# Temp_Bank.net
KiCad netlist of a schematic drawn in Altium Designer
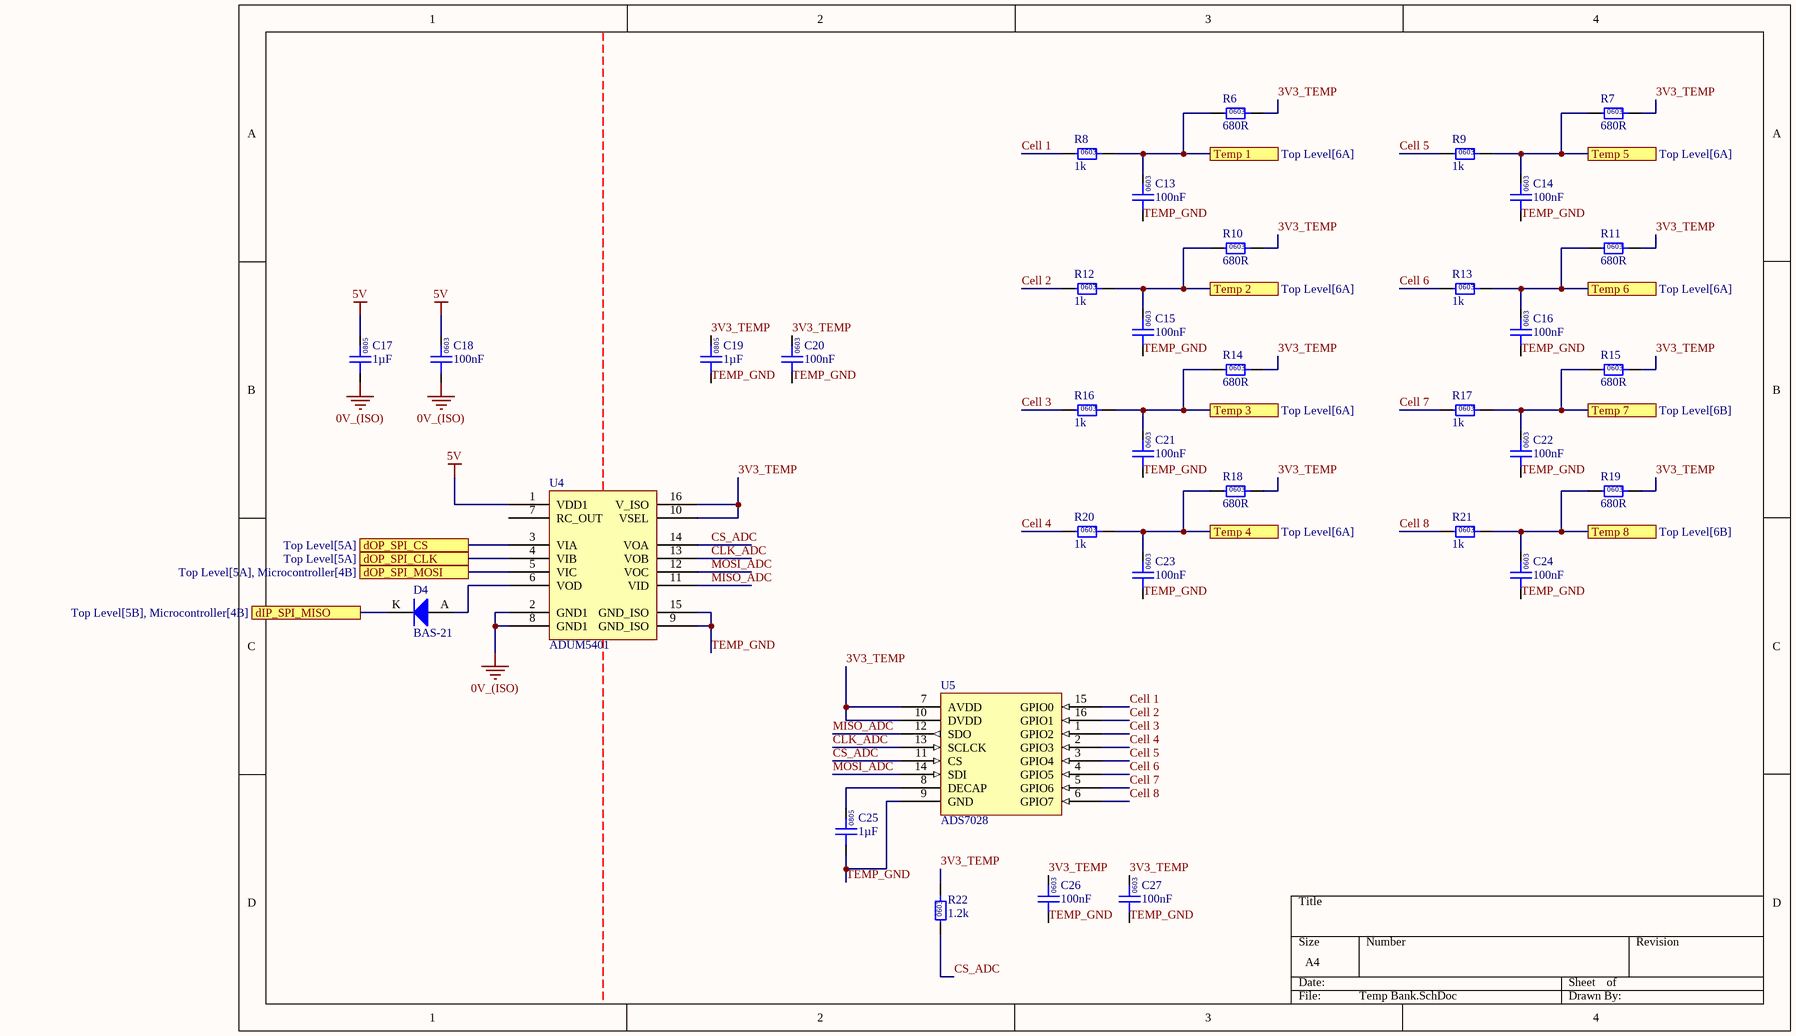
[diagram p0: Temp Bank.SchDoc]

(export (version "E")
  (design (tool "Eeschema 10.0.6"))
  (components
    (comp (ref "C13")
      (value "100nF")
      (footprint "0603")
      (fields
        (field (name "PART NUMBER") "GCM188L81H104KA57D")
        (field (name "MANUFACTURER") "muRata")
        (field (name "TOLERANCE") "±10%")
      )
      (libsource (lib "ts_standard_library") (part "Capacitor 0603"))
    )
    (comp (ref "C14")
      (value "100nF")
      (footprint "0603")
      (fields
        (field (name "PART NUMBER") "GCM188L81H104KA57D")
        (field (name "MANUFACTURER") "muRata")
        (field (name "TOLERANCE") "±10%")
      )
      (libsource (lib "ts_standard_library") (part "Capacitor 0603"))
    )
    (comp (ref "C15")
      (value "100nF")
      (footprint "0603")
      (fields
        (field (name "PART NUMBER") "GCM188L81H104KA57D")
        (field (name "MANUFACTURER") "muRata")
        (field (name "TOLERANCE") "±10%")
      )
      (libsource (lib "ts_standard_library") (part "Capacitor 0603"))
    )
    (comp (ref "C16")
      (value "100nF")
      (footprint "0603")
      (fields
        (field (name "PART NUMBER") "GCM188L81H104KA57D")
        (field (name "MANUFACTURER") "muRata")
        (field (name "TOLERANCE") "±10%")
      )
      (libsource (lib "ts_standard_library") (part "Capacitor 0603"))
    )
    (comp (ref "C17")
      (value "1µF")
      (footprint "0805")
      (fields
        (field (name "PART NUMBER") "GCM21BR71H105KA03L")
        (field (name "MANUFACTURER") "muRata")
        (field (name "TOLERANCE") "±10%")
      )
      (libsource (lib "ts_standard_library") (part "Capacitor 0805"))
    )
    (comp (ref "C18")
      (value "100nF")
      (footprint "0603")
      (fields
        (field (name "PART NUMBER") "GCM188L81H104KA57D")
        (field (name "MANUFACTURER") "muRata")
        (field (name "TOLERANCE") "±10%")
      )
      (libsource (lib "ts_standard_library") (part "Capacitor 0603"))
    )
    (comp (ref "C19")
      (value "1µF")
      (footprint "0805")
      (fields
        (field (name "PART NUMBER") "GCM21BR71H105KA03L")
        (field (name "MANUFACTURER") "muRata")
        (field (name "TOLERANCE") "±10%")
      )
      (libsource (lib "ts_standard_library") (part "Capacitor 0805"))
    )
    (comp (ref "C20")
      (value "100nF")
      (footprint "0603")
      (fields
        (field (name "PART NUMBER") "GCM188L81H104KA57D")
        (field (name "MANUFACTURER") "muRata")
        (field (name "TOLERANCE") "±10%")
      )
      (libsource (lib "ts_standard_library") (part "Capacitor 0603"))
    )
    (comp (ref "C21")
      (value "100nF")
      (footprint "0603")
      (fields
        (field (name "PART NUMBER") "GCM188L81H104KA57D")
        (field (name "MANUFACTURER") "muRata")
        (field (name "TOLERANCE") "±10%")
      )
      (libsource (lib "ts_standard_library") (part "Capacitor 0603"))
    )
    (comp (ref "C22")
      (value "100nF")
      (footprint "0603")
      (fields
        (field (name "PART NUMBER") "GCM188L81H104KA57D")
        (field (name "MANUFACTURER") "muRata")
        (field (name "TOLERANCE") "±10%")
      )
      (libsource (lib "ts_standard_library") (part "Capacitor 0603"))
    )
    (comp (ref "C23")
      (value "100nF")
      (footprint "0603")
      (fields
        (field (name "PART NUMBER") "GCM188L81H104KA57D")
        (field (name "MANUFACTURER") "muRata")
        (field (name "TOLERANCE") "±10%")
      )
      (libsource (lib "ts_standard_library") (part "Capacitor 0603"))
    )
    (comp (ref "C24")
      (value "100nF")
      (footprint "0603")
      (fields
        (field (name "PART NUMBER") "GCM188L81H104KA57D")
        (field (name "MANUFACTURER") "muRata")
        (field (name "TOLERANCE") "±10%")
      )
      (libsource (lib "ts_standard_library") (part "Capacitor 0603"))
    )
    (comp (ref "C25")
      (value "1µF")
      (footprint "0805")
      (fields
        (field (name "PART NUMBER") "GCM21BR71H105KA03L")
        (field (name "MANUFACTURER") "muRata")
        (field (name "TOLERANCE") "±10%")
      )
      (libsource (lib "ts_standard_library") (part "Capacitor 0805"))
    )
    (comp (ref "C26")
      (value "100nF")
      (footprint "0603")
      (fields
        (field (name "PART NUMBER") "GCM188L81H104KA57D")
        (field (name "MANUFACTURER") "muRata")
        (field (name "TOLERANCE") "±10%")
      )
      (libsource (lib "ts_standard_library") (part "Capacitor 0603"))
    )
    (comp (ref "C27")
      (value "100nF")
      (footprint "0603")
      (fields
        (field (name "PART NUMBER") "GCM188L81H104KA57D")
        (field (name "MANUFACTURER") "muRata")
        (field (name "TOLERANCE") "±10%")
      )
      (libsource (lib "ts_standard_library") (part "Capacitor 0603"))
    )
    (comp (ref "D4")
      (value "BAS-21")
      (footprint "NEXPERIA_SOT23")
      (fields (field (name "MANUFACTURER") "Nexperia USA Inc."))
      (libsource (lib "ts_standard_library") (part "Diode"))
    )
    (comp (ref "R6")
      (value "680R")
      (footprint "0603")
      (fields
        (field (name "PART NUMBER") "RC0603JR-13680RL")
        (field (name "MANUFACTURER") "YAGEO")
        (field (name "TOLERANCE") "0.01")
      )
      (libsource (lib "ts_standard_library") (part "Resistor 0603"))
    )
    (comp (ref "R7")
      (value "680R")
      (footprint "0603")
      (fields
        (field (name "PART NUMBER") "RC0603JR-13680RL")
        (field (name "MANUFACTURER") "YAGEO")
        (field (name "TOLERANCE") "0.01")
      )
      (libsource (lib "ts_standard_library") (part "Resistor 0603"))
    )
    (comp (ref "R8")
      (value "1k")
      (footprint "0603")
      (fields
        (field (name "PART NUMBER") "RC0603FR-071KL")
        (field (name "MANUFACTURER") "YAGEO")
        (field (name "TOLERANCE") "0.01")
      )
      (libsource (lib "ts_standard_library") (part "Resistor 0603"))
    )
    (comp (ref "R9")
      (value "1k")
      (footprint "0603")
      (fields
        (field (name "PART NUMBER") "RC0603FR-071KL")
        (field (name "MANUFACTURER") "YAGEO")
        (field (name "TOLERANCE") "0.01")
      )
      (libsource (lib "ts_standard_library") (part "Resistor 0603"))
    )
    (comp (ref "R10")
      (value "680R")
      (footprint "0603")
      (fields
        (field (name "PART NUMBER") "RC0603JR-13680RL")
        (field (name "MANUFACTURER") "YAGEO")
        (field (name "TOLERANCE") "0.01")
      )
      (libsource (lib "ts_standard_library") (part "Resistor 0603"))
    )
    (comp (ref "R11")
      (value "680R")
      (footprint "0603")
      (fields
        (field (name "PART NUMBER") "RC0603JR-13680RL")
        (field (name "MANUFACTURER") "YAGEO")
        (field (name "TOLERANCE") "0.01")
      )
      (libsource (lib "ts_standard_library") (part "Resistor 0603"))
    )
    (comp (ref "R12")
      (value "1k")
      (footprint "0603")
      (fields
        (field (name "PART NUMBER") "RC0603FR-071KL")
        (field (name "MANUFACTURER") "YAGEO")
        (field (name "TOLERANCE") "0.01")
      )
      (libsource (lib "ts_standard_library") (part "Resistor 0603"))
    )
    (comp (ref "R13")
      (value "1k")
      (footprint "0603")
      (fields
        (field (name "PART NUMBER") "RC0603FR-071KL")
        (field (name "MANUFACTURER") "YAGEO")
        (field (name "TOLERANCE") "0.01")
      )
      (libsource (lib "ts_standard_library") (part "Resistor 0603"))
    )
    (comp (ref "R14")
      (value "680R")
      (footprint "0603")
      (fields
        (field (name "PART NUMBER") "RC0603JR-13680RL")
        (field (name "MANUFACTURER") "YAGEO")
        (field (name "TOLERANCE") "0.01")
      )
      (libsource (lib "ts_standard_library") (part "Resistor 0603"))
    )
    (comp (ref "R15")
      (value "680R")
      (footprint "0603")
      (fields
        (field (name "PART NUMBER") "RC0603JR-13680RL")
        (field (name "MANUFACTURER") "YAGEO")
        (field (name "TOLERANCE") "0.01")
      )
      (libsource (lib "ts_standard_library") (part "Resistor 0603"))
    )
    (comp (ref "R16")
      (value "1k")
      (footprint "0603")
      (fields
        (field (name "PART NUMBER") "RC0603FR-071KL")
        (field (name "MANUFACTURER") "YAGEO")
        (field (name "TOLERANCE") "0.01")
      )
      (libsource (lib "ts_standard_library") (part "Resistor 0603"))
    )
    (comp (ref "R17")
      (value "1k")
      (footprint "0603")
      (fields
        (field (name "PART NUMBER") "RC0603FR-071KL")
        (field (name "MANUFACTURER") "YAGEO")
        (field (name "TOLERANCE") "0.01")
      )
      (libsource (lib "ts_standard_library") (part "Resistor 0603"))
    )
    (comp (ref "R18")
      (value "680R")
      (footprint "0603")
      (fields
        (field (name "PART NUMBER") "RC0603JR-13680RL")
        (field (name "MANUFACTURER") "YAGEO")
        (field (name "TOLERANCE") "0.01")
      )
      (libsource (lib "ts_standard_library") (part "Resistor 0603"))
    )
    (comp (ref "R19")
      (value "680R")
      (footprint "0603")
      (fields
        (field (name "PART NUMBER") "RC0603JR-13680RL")
        (field (name "MANUFACTURER") "YAGEO")
        (field (name "TOLERANCE") "0.01")
      )
      (libsource (lib "ts_standard_library") (part "Resistor 0603"))
    )
    (comp (ref "R20")
      (value "1k")
      (footprint "0603")
      (fields
        (field (name "PART NUMBER") "RC0603FR-071KL")
        (field (name "MANUFACTURER") "YAGEO")
        (field (name "TOLERANCE") "0.01")
      )
      (libsource (lib "ts_standard_library") (part "Resistor 0603"))
    )
    (comp (ref "R21")
      (value "1k")
      (footprint "0603")
      (fields
        (field (name "PART NUMBER") "RC0603FR-071KL")
        (field (name "MANUFACTURER") "YAGEO")
        (field (name "TOLERANCE") "0.01")
      )
      (libsource (lib "ts_standard_library") (part "Resistor 0603"))
    )
    (comp (ref "R22")
      (value "1.2k")
      (footprint "0603")
      (fields
        (field (name "PART NUMBER") "RC0603JR-071K2L")
        (field (name "MANUFACTURER") "YAGEO")
        (field (name "TOLERANCE") "0.01")
      )
      (libsource (lib "ts_standard_library") (part "Resistor 0603"))
    )
    (comp (ref "U4")
      (value "ADUM5401")
      (footprint "AD 16-SOIC")
      (description "Quad Channel 2.5kV Digital Isolator with isoPower")
      (fields (field (name "MANUFACTURER") "Analogue Devices"))
      (libsource (lib "ts_standard_library") (part "ADUM5401"))
    )
    (comp (ref "U5")
      (value "ADS7028")
      (footprint "WFQN-16")
      (description "IC ADC 12BIT SAR 16WQFN")
      (fields (field (name "PART NUMBER") "ADS7028IRTER") (field (name "MANUFACTURER") "Texas Instruments"))
      (libsource (lib "ts_standard_library") (part "ADS7028IRTER"))
    )
  )
  (nets
    (net (code "1") (name "/3V3_TEMP") (class "Default")
      (node (ref "C19") (pin "2") (pinfunction "2_2") (pintype "passive"))
      (node (ref "C20") (pin "2") (pinfunction "2_2") (pintype "passive"))
      (node (ref "C26") (pin "2") (pinfunction "2_2") (pintype "passive"))
      (node (ref "C27") (pin "2") (pinfunction "2_2") (pintype "passive"))
      (node (ref "R10") (pin "2") (pinfunction "2_2") (pintype "passive"))
      (node (ref "R11") (pin "2") (pinfunction "2_2") (pintype "passive"))
      (node (ref "R14") (pin "2") (pinfunction "2_2") (pintype "passive"))
      (node (ref "R15") (pin "2") (pinfunction "2_2") (pintype "passive"))
      (node (ref "R18") (pin "2") (pinfunction "2_2") (pintype "passive"))
      (node (ref "R19") (pin "2") (pinfunction "2_2") (pintype "passive"))
      (node (ref "R22") (pin "2") (pinfunction "2_2") (pintype "passive"))
      (node (ref "R6") (pin "2") (pinfunction "2_2") (pintype "passive"))
      (node (ref "R7") (pin "2") (pinfunction "2_2") (pintype "passive"))
      (node (ref "U4") (pin "10") (pinfunction "VSEL_10") (pintype "passive"))
      (node (ref "U4") (pin "16") (pinfunction "V_ISO_16") (pintype "passive"))
      (node (ref "U5") (pin "10") (pinfunction "DVDD_10") (pintype "power_in"))
      (node (ref "U5") (pin "7") (pinfunction "AVDD_7") (pintype "power_in"))
    )
    (net (code "2") (name "/CLK_ADC") (class "Default")
      (node (ref "U4") (pin "13") (pinfunction "VOB_13") (pintype "passive"))
      (node (ref "U5") (pin "13") (pinfunction "SCLCK_13") (pintype "input"))
    )
    (net (code "3") (name "/CS_ADC") (class "Default")
      (node (ref "R22") (pin "1") (pinfunction "1_1") (pintype "passive"))
      (node (ref "U4") (pin "14") (pinfunction "VOA_14") (pintype "passive"))
      (node (ref "U5") (pin "11") (pinfunction "CS_11") (pintype "input"))
    )
    (net (code "4") (name "/Cell 1") (class "Default")
      (node (ref "R8") (pin "1") (pinfunction "1_1") (pintype "passive"))
      (node (ref "U5") (pin "15") (pinfunction "GPIO0_15") (pintype "input"))
    )
    (net (code "5") (name "/Cell 2") (class "Default")
      (node (ref "R12") (pin "1") (pinfunction "1_1") (pintype "passive"))
      (node (ref "U5") (pin "16") (pinfunction "GPIO1_16") (pintype "input"))
    )
    (net (code "6") (name "/Cell 3") (class "Default")
      (node (ref "R16") (pin "1") (pinfunction "1_1") (pintype "passive"))
      (node (ref "U5") (pin "1") (pinfunction "GPIO2_1") (pintype "input"))
    )
    (net (code "7") (name "/Cell 4") (class "Default")
      (node (ref "R20") (pin "1") (pinfunction "1_1") (pintype "passive"))
      (node (ref "U5") (pin "2") (pinfunction "GPIO3_2") (pintype "input"))
    )
    (net (code "8") (name "/Cell 5") (class "Default")
      (node (ref "R9") (pin "1") (pinfunction "1_1") (pintype "passive"))
      (node (ref "U5") (pin "3") (pinfunction "GPIO4_3") (pintype "input"))
    )
    (net (code "9") (name "/Cell 6") (class "Default")
      (node (ref "R13") (pin "1") (pinfunction "1_1") (pintype "passive"))
      (node (ref "U5") (pin "4") (pinfunction "GPIO5_4") (pintype "input"))
    )
    (net (code "10") (name "/Cell 7") (class "Default")
      (node (ref "R17") (pin "1") (pinfunction "1_1") (pintype "passive"))
      (node (ref "U5") (pin "5") (pinfunction "GPIO6_5") (pintype "input"))
    )
    (net (code "11") (name "/Cell 8") (class "Default")
      (node (ref "R21") (pin "1") (pinfunction "1_1") (pintype "passive"))
      (node (ref "U5") (pin "6") (pinfunction "GPIO7_6") (pintype "input"))
    )
    (net (code "12") (name "/MISO_ADC") (class "Default")
      (node (ref "U4") (pin "11") (pinfunction "VID_11") (pintype "passive"))
      (node (ref "U5") (pin "12") (pinfunction "SDO_12") (pintype "output"))
    )
    (net (code "13") (name "/MOSI_ADC") (class "Default")
      (node (ref "U4") (pin "12") (pinfunction "VOC_12") (pintype "passive"))
      (node (ref "U5") (pin "14") (pinfunction "SDI_14") (pintype "input"))
    )
    (net (code "14") (name "/TEMP_GND") (class "Default")
      (node (ref "C13") (pin "1") (pinfunction "1_1") (pintype "passive"))
      (node (ref "C14") (pin "1") (pinfunction "1_1") (pintype "passive"))
      (node (ref "C15") (pin "1") (pinfunction "1_1") (pintype "passive"))
      (node (ref "C16") (pin "1") (pinfunction "1_1") (pintype "passive"))
      (node (ref "C19") (pin "1") (pinfunction "1_1") (pintype "passive"))
      (node (ref "C20") (pin "1") (pinfunction "1_1") (pintype "passive"))
      (node (ref "C21") (pin "1") (pinfunction "1_1") (pintype "passive"))
      (node (ref "C22") (pin "1") (pinfunction "1_1") (pintype "passive"))
      (node (ref "C23") (pin "1") (pinfunction "1_1") (pintype "passive"))
      (node (ref "C24") (pin "1") (pinfunction "1_1") (pintype "passive"))
      (node (ref "C25") (pin "1") (pinfunction "1_1") (pintype "passive"))
      (node (ref "C26") (pin "1") (pinfunction "1_1") (pintype "passive"))
      (node (ref "C27") (pin "1") (pinfunction "1_1") (pintype "passive"))
      (node (ref "U4") (pin "15") (pinfunction "GND_ISO_15") (pintype "passive"))
      (node (ref "U4") (pin "9") (pinfunction "GND_ISO_9") (pintype "passive"))
      (node (ref "U5") (pin "9") (pinfunction "GND_9") (pintype "power_in"))
    )
    (net (code "15") (name "/Temp 1") (class "Default")
      (node (ref "C13") (pin "2") (pinfunction "2_2") (pintype "passive"))
      (node (ref "R6") (pin "1") (pinfunction "1_1") (pintype "passive"))
      (node (ref "R8") (pin "2") (pinfunction "2_2") (pintype "passive"))
    )
    (net (code "16") (name "/Temp 2") (class "Default")
      (node (ref "C15") (pin "2") (pinfunction "2_2") (pintype "passive"))
      (node (ref "R10") (pin "1") (pinfunction "1_1") (pintype "passive"))
      (node (ref "R12") (pin "2") (pinfunction "2_2") (pintype "passive"))
    )
    (net (code "17") (name "/Temp 3") (class "Default")
      (node (ref "C21") (pin "2") (pinfunction "2_2") (pintype "passive"))
      (node (ref "R14") (pin "1") (pinfunction "1_1") (pintype "passive"))
      (node (ref "R16") (pin "2") (pinfunction "2_2") (pintype "passive"))
    )
    (net (code "18") (name "/Temp 4") (class "Default")
      (node (ref "C23") (pin "2") (pinfunction "2_2") (pintype "passive"))
      (node (ref "R18") (pin "1") (pinfunction "1_1") (pintype "passive"))
      (node (ref "R20") (pin "2") (pinfunction "2_2") (pintype "passive"))
    )
    (net (code "19") (name "/Temp 5") (class "Default")
      (node (ref "C14") (pin "2") (pinfunction "2_2") (pintype "passive"))
      (node (ref "R7") (pin "1") (pinfunction "1_1") (pintype "passive"))
      (node (ref "R9") (pin "2") (pinfunction "2_2") (pintype "passive"))
    )
    (net (code "20") (name "/Temp 6") (class "Default")
      (node (ref "C16") (pin "2") (pinfunction "2_2") (pintype "passive"))
      (node (ref "R11") (pin "1") (pinfunction "1_1") (pintype "passive"))
      (node (ref "R13") (pin "2") (pinfunction "2_2") (pintype "passive"))
    )
    (net (code "21") (name "/Temp 7") (class "Default")
      (node (ref "C22") (pin "2") (pinfunction "2_2") (pintype "passive"))
      (node (ref "R15") (pin "1") (pinfunction "1_1") (pintype "passive"))
      (node (ref "R17") (pin "2") (pinfunction "2_2") (pintype "passive"))
    )
    (net (code "22") (name "/Temp 8") (class "Default")
      (node (ref "C24") (pin "2") (pinfunction "2_2") (pintype "passive"))
      (node (ref "R19") (pin "1") (pinfunction "1_1") (pintype "passive"))
      (node (ref "R21") (pin "2") (pinfunction "2_2") (pintype "passive"))
    )
    (net (code "23") (name "/dIP_SPI_MISO") (class "Default")
      (node (ref "D4") (pin "K") (pinfunction "K_K") (pintype "passive"))
    )
    (net (code "24") (name "/dOP_SPI_CLK") (class "Default")
      (node (ref "U4") (pin "4") (pinfunction "VIB_4") (pintype "passive"))
    )
    (net (code "25") (name "/dOP_SPI_CS") (class "Default")
      (node (ref "U4") (pin "3") (pinfunction "VIA_3") (pintype "passive"))
    )
    (net (code "26") (name "/dOP_SPI_MOSI") (class "Default")
      (node (ref "U4") (pin "5") (pinfunction "VIC_5") (pintype "passive"))
    )
    (net (code "27") (name "0V_(ISO)") (class "Default")
      (node (ref "C17") (pin "1") (pinfunction "1_1") (pintype "passive"))
      (node (ref "C18") (pin "1") (pinfunction "1_1") (pintype "passive"))
      (node (ref "U4") (pin "2") (pinfunction "GND1_2") (pintype "passive"))
      (node (ref "U4") (pin "8") (pinfunction "GND1_8") (pintype "passive"))
    )
    (net (code "28") (name "5V") (class "Default")
      (node (ref "C17") (pin "2") (pinfunction "2_2") (pintype "passive"))
      (node (ref "C18") (pin "2") (pinfunction "2_2") (pintype "passive"))
      (node (ref "U4") (pin "1") (pinfunction "VDD1_1") (pintype "passive"))
    )
    (net (code "29") (name "Net-(U4-VOD)") (class "Default")
      (node (ref "D4") (pin "A") (pinfunction "A_A") (pintype "passive"))
      (node (ref "U4") (pin "6") (pinfunction "VOD_6") (pintype "passive"))
    )
    (net (code "30") (name "Net-(U5-DECAP)") (class "Default")
      (node (ref "C25") (pin "2") (pinfunction "2_2") (pintype "passive"))
      (node (ref "U5") (pin "8") (pinfunction "DECAP_8") (pintype "power_in"))
    )
    (net (code "31") (name "unconnected-(U4-RC_OUT-Pad7)") (class "Default")
      (node (ref "U4") (pin "7") (pinfunction "RC_OUT_7") (pintype "passive"))
    )
  )
)
